# STM32F108VBT6_2.net
KiCad netlist of a schematic drawn in Altium Designer
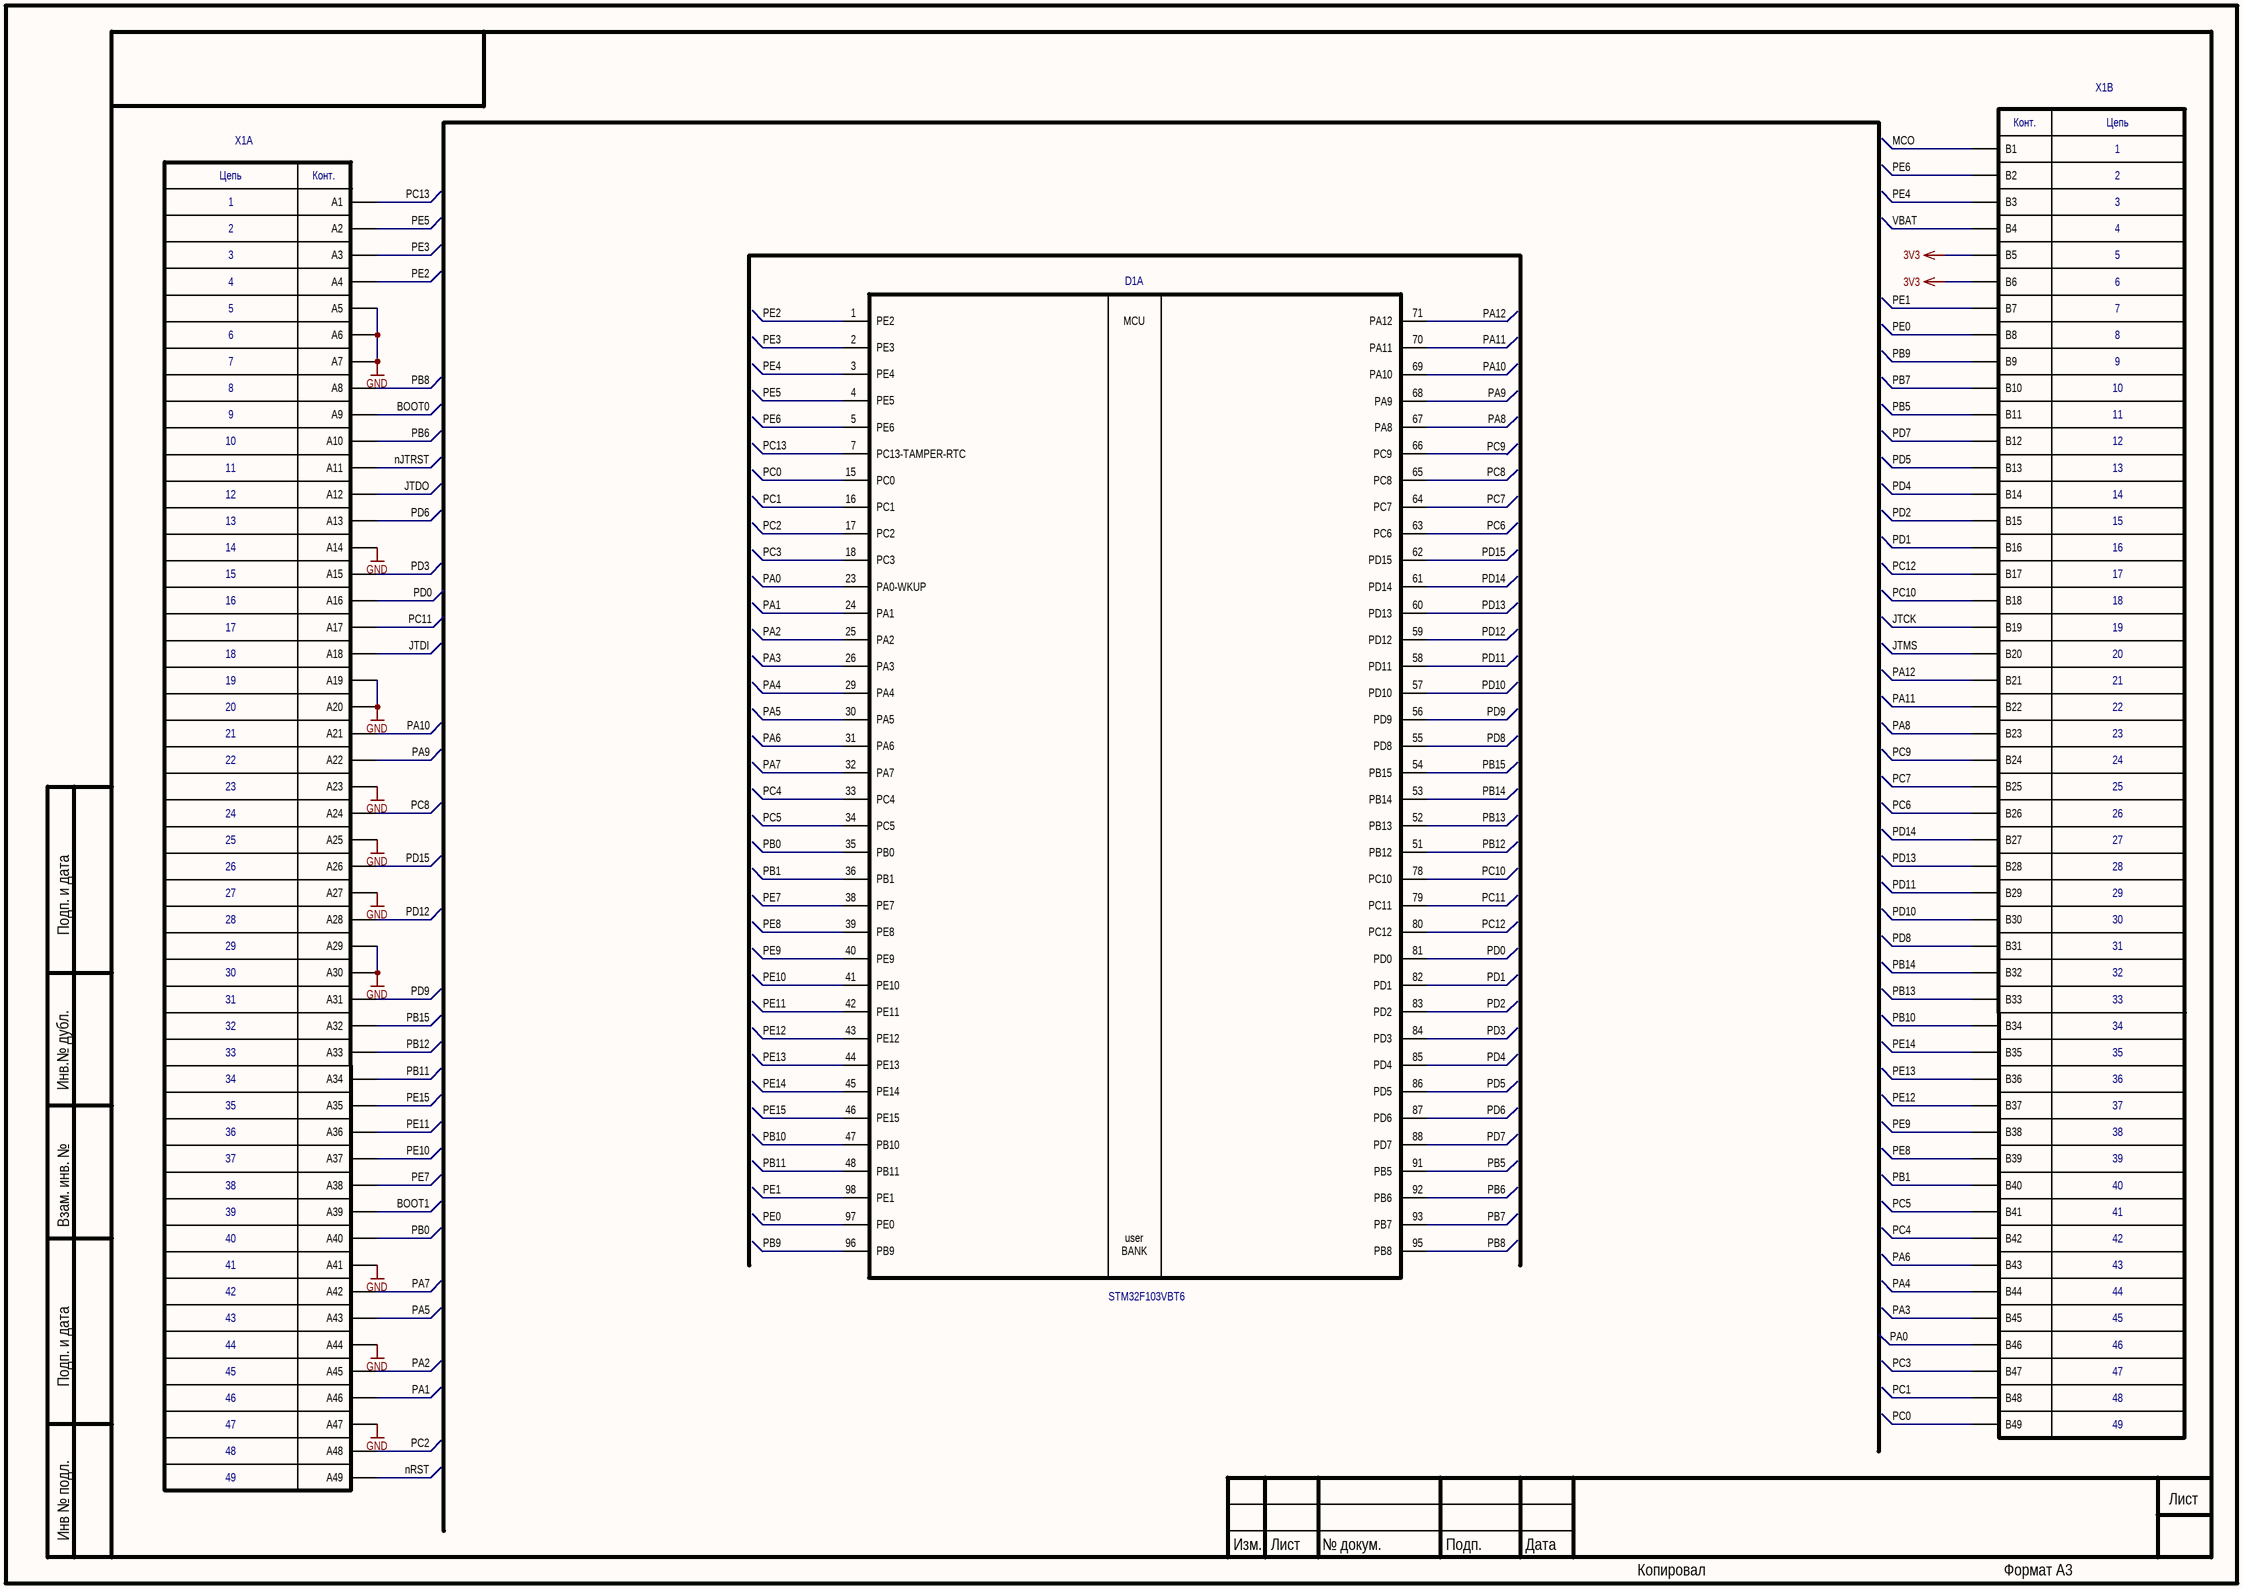
[diagram p0: Модуль STM32F108VBT6_2.SchDoc]

(export (version "E")
  (design (tool "Eeschema 10.0.6"))
  (components
    (comp (ref "D1")
      (value "STM32F103VBT6")
      (footprint "QFP50P1600X1600X160-100N")
      (fields (field (name "Comment") " (LQFP-48) Xilinx"))
      (libsource (lib "Lisaveta_SCH") (part "STM32F103VBT6"))
    )
    (comp (ref "X1")
      (value "KONT_POLE_MEZ")
      (footprint "3113-112t_otv")
      (libsource (lib "Lisaveta_SCH") (part "3113-112T"))
    )
  )
  (nets
    (net (code "1") (name "/BOOT0") (class "Default")
      (node (ref "X1") (pin "A9") (pinfunction "A9_A9") (pintype "passive"))
    )
    (net (code "2") (name "/BOOT1") (class "Default")
      (node (ref "X1") (pin "A39") (pinfunction "A39_A39") (pintype "passive"))
    )
    (net (code "3") (name "/JTCK") (class "Default")
      (node (ref "X1") (pin "B19") (pinfunction "B19_B19") (pintype "passive"))
    )
    (net (code "4") (name "/JTDI") (class "Default")
      (node (ref "X1") (pin "A18") (pinfunction "A18_A18") (pintype "passive"))
    )
    (net (code "5") (name "/JTDO") (class "Default")
      (node (ref "X1") (pin "A12") (pinfunction "A12_A12") (pintype "passive"))
    )
    (net (code "6") (name "/JTMS") (class "Default")
      (node (ref "X1") (pin "B20") (pinfunction "B20_B20") (pintype "passive"))
    )
    (net (code "7") (name "/MCO") (class "Default")
      (node (ref "X1") (pin "B1") (pinfunction "B1_B1") (pintype "passive"))
    )
    (net (code "8") (name "/PA0") (class "Default")
      (node (ref "D1") (pin "23") (pinfunction "PA0-WKUP_23") (pintype "passive"))
      (node (ref "X1") (pin "B46") (pinfunction "B46_B46") (pintype "passive"))
    )
    (net (code "9") (name "/PA1") (class "Default")
      (node (ref "D1") (pin "24") (pinfunction "PA1_24") (pintype "passive"))
      (node (ref "X1") (pin "A46") (pinfunction "A46_A46") (pintype "passive"))
    )
    (net (code "10") (name "/PA2") (class "Default")
      (node (ref "D1") (pin "25") (pinfunction "PA2_25") (pintype "passive"))
      (node (ref "X1") (pin "A45") (pinfunction "A45_A45") (pintype "passive"))
    )
    (net (code "11") (name "/PA3") (class "Default")
      (node (ref "D1") (pin "26") (pinfunction "PA3_26") (pintype "passive"))
      (node (ref "X1") (pin "B45") (pinfunction "B45_B45") (pintype "passive"))
    )
    (net (code "12") (name "/PA4") (class "Default")
      (node (ref "D1") (pin "29") (pinfunction "PA4_29") (pintype "passive"))
      (node (ref "X1") (pin "B44") (pinfunction "B44_B44") (pintype "passive"))
    )
    (net (code "13") (name "/PA5") (class "Default")
      (node (ref "D1") (pin "30") (pinfunction "PA5_30") (pintype "passive"))
      (node (ref "X1") (pin "A43") (pinfunction "A43_A43") (pintype "passive"))
    )
    (net (code "14") (name "/PA6") (class "Default")
      (node (ref "D1") (pin "31") (pinfunction "PA6_31") (pintype "passive"))
      (node (ref "X1") (pin "B43") (pinfunction "B43_B43") (pintype "passive"))
    )
    (net (code "15") (name "/PA7") (class "Default")
      (node (ref "D1") (pin "32") (pinfunction "PA7_32") (pintype "passive"))
      (node (ref "X1") (pin "A42") (pinfunction "A42_A42") (pintype "passive"))
    )
    (net (code "16") (name "/PA8") (class "Default")
      (node (ref "D1") (pin "67") (pinfunction "PA8_67") (pintype "passive"))
      (node (ref "X1") (pin "B23") (pinfunction "B23_B23") (pintype "passive"))
    )
    (net (code "17") (name "/PA9") (class "Default")
      (node (ref "D1") (pin "68") (pinfunction "PA9_68") (pintype "passive"))
      (node (ref "X1") (pin "A22") (pinfunction "A22_A22") (pintype "passive"))
    )
    (net (code "18") (name "/PA10") (class "Default")
      (node (ref "D1") (pin "69") (pinfunction "PA10_69") (pintype "passive"))
      (node (ref "X1") (pin "A21") (pinfunction "A21_A21") (pintype "passive"))
    )
    (net (code "19") (name "/PA11") (class "Default")
      (node (ref "D1") (pin "70") (pinfunction "PA11_70") (pintype "passive"))
      (node (ref "X1") (pin "B22") (pinfunction "B22_B22") (pintype "passive"))
    )
    (net (code "20") (name "/PA12") (class "Default")
      (node (ref "D1") (pin "71") (pinfunction "PA12_71") (pintype "passive"))
      (node (ref "X1") (pin "B21") (pinfunction "B21_B21") (pintype "passive"))
    )
    (net (code "21") (name "/PB0") (class "Default")
      (node (ref "D1") (pin "35") (pinfunction "PB0_35") (pintype "passive"))
      (node (ref "X1") (pin "A40") (pinfunction "A40_A40") (pintype "passive"))
    )
    (net (code "22") (name "/PB1") (class "Default")
      (node (ref "D1") (pin "36") (pinfunction "PB1_36") (pintype "passive"))
      (node (ref "X1") (pin "B40") (pinfunction "B40_B40") (pintype "passive"))
    )
    (net (code "23") (name "/PB5") (class "Default")
      (node (ref "D1") (pin "91") (pinfunction "PB5_91") (pintype "passive"))
      (node (ref "X1") (pin "B11") (pinfunction "B11_B11") (pintype "passive"))
    )
    (net (code "24") (name "/PB6") (class "Default")
      (node (ref "D1") (pin "92") (pinfunction "PB6_92") (pintype "passive"))
      (node (ref "X1") (pin "A10") (pinfunction "A10_A10") (pintype "passive"))
    )
    (net (code "25") (name "/PB7") (class "Default")
      (node (ref "D1") (pin "93") (pinfunction "PB7_93") (pintype "passive"))
      (node (ref "X1") (pin "B10") (pinfunction "B10_B10") (pintype "passive"))
    )
    (net (code "26") (name "/PB8") (class "Default")
      (node (ref "D1") (pin "95") (pinfunction "PB8_95") (pintype "passive"))
      (node (ref "X1") (pin "A8") (pinfunction "A8_A8") (pintype "passive"))
    )
    (net (code "27") (name "/PB9") (class "Default")
      (node (ref "D1") (pin "96") (pinfunction "PB9_96") (pintype "passive"))
      (node (ref "X1") (pin "B9") (pinfunction "B9_B9") (pintype "passive"))
    )
    (net (code "28") (name "/PB10") (class "Default")
      (node (ref "D1") (pin "47") (pinfunction "PB10_47") (pintype "passive"))
      (node (ref "X1") (pin "B34") (pinfunction "B34_B34") (pintype "passive"))
    )
    (net (code "29") (name "/PB11") (class "Default")
      (node (ref "D1") (pin "48") (pinfunction "PB11_48") (pintype "passive"))
      (node (ref "X1") (pin "A34") (pinfunction "A34_A34") (pintype "passive"))
    )
    (net (code "30") (name "/PB12") (class "Default")
      (node (ref "D1") (pin "51") (pinfunction "PB12_51") (pintype "passive"))
      (node (ref "X1") (pin "A33") (pinfunction "A33_A33") (pintype "passive"))
    )
    (net (code "31") (name "/PB13") (class "Default")
      (node (ref "D1") (pin "52") (pinfunction "PB13_52") (pintype "passive"))
      (node (ref "X1") (pin "B33") (pinfunction "B33_B33") (pintype "passive"))
    )
    (net (code "32") (name "/PB14") (class "Default")
      (node (ref "D1") (pin "53") (pinfunction "PB14_53") (pintype "passive"))
      (node (ref "X1") (pin "B32") (pinfunction "B32_B32") (pintype "passive"))
    )
    (net (code "33") (name "/PB15") (class "Default")
      (node (ref "D1") (pin "54") (pinfunction "PB15_54") (pintype "passive"))
      (node (ref "X1") (pin "A32") (pinfunction "A32_A32") (pintype "passive"))
    )
    (net (code "34") (name "/PC0") (class "Default")
      (node (ref "D1") (pin "15") (pinfunction "PC0_15") (pintype "passive"))
      (node (ref "X1") (pin "B49") (pinfunction "B49_B49") (pintype "passive"))
    )
    (net (code "35") (name "/PC1") (class "Default")
      (node (ref "D1") (pin "16") (pinfunction "PC1_16") (pintype "passive"))
      (node (ref "X1") (pin "B48") (pinfunction "B48_B48") (pintype "passive"))
    )
    (net (code "36") (name "/PC2") (class "Default")
      (node (ref "D1") (pin "17") (pinfunction "PC2_17") (pintype "passive"))
      (node (ref "X1") (pin "A48") (pinfunction "A48_A48") (pintype "passive"))
    )
    (net (code "37") (name "/PC3") (class "Default")
      (node (ref "D1") (pin "18") (pinfunction "PC3_18") (pintype "passive"))
      (node (ref "X1") (pin "B47") (pinfunction "B47_B47") (pintype "passive"))
    )
    (net (code "38") (name "/PC4") (class "Default")
      (node (ref "D1") (pin "33") (pinfunction "PC4_33") (pintype "passive"))
      (node (ref "X1") (pin "B42") (pinfunction "B42_B42") (pintype "passive"))
    )
    (net (code "39") (name "/PC5") (class "Default")
      (node (ref "D1") (pin "34") (pinfunction "PC5_34") (pintype "passive"))
      (node (ref "X1") (pin "B41") (pinfunction "B41_B41") (pintype "passive"))
    )
    (net (code "40") (name "/PC6") (class "Default")
      (node (ref "D1") (pin "63") (pinfunction "PC6_63") (pintype "passive"))
      (node (ref "X1") (pin "B26") (pinfunction "B26_B26") (pintype "passive"))
    )
    (net (code "41") (name "/PC7") (class "Default")
      (node (ref "D1") (pin "64") (pinfunction "PC7_64") (pintype "passive"))
      (node (ref "X1") (pin "B25") (pinfunction "B25_B25") (pintype "passive"))
    )
    (net (code "42") (name "/PC8") (class "Default")
      (node (ref "D1") (pin "65") (pinfunction "PC8_65") (pintype "passive"))
      (node (ref "X1") (pin "A24") (pinfunction "A24_A24") (pintype "passive"))
    )
    (net (code "43") (name "/PC9") (class "Default")
      (node (ref "D1") (pin "66") (pinfunction "PC9_66") (pintype "passive"))
      (node (ref "X1") (pin "B24") (pinfunction "B24_B24") (pintype "passive"))
    )
    (net (code "44") (name "/PC10") (class "Default")
      (node (ref "D1") (pin "78") (pinfunction "PC10_78") (pintype "passive"))
      (node (ref "X1") (pin "B18") (pinfunction "B18_B18") (pintype "passive"))
    )
    (net (code "45") (name "/PC11") (class "Default")
      (node (ref "D1") (pin "79") (pinfunction "PC11_79") (pintype "passive"))
      (node (ref "X1") (pin "A17") (pinfunction "A17_A17") (pintype "passive"))
    )
    (net (code "46") (name "/PC12") (class "Default")
      (node (ref "D1") (pin "80") (pinfunction "PC12_80") (pintype "passive"))
      (node (ref "X1") (pin "B17") (pinfunction "B17_B17") (pintype "passive"))
    )
    (net (code "47") (name "/PC13") (class "Default")
      (node (ref "D1") (pin "7") (pinfunction "PC13-TAMPER-RTC_7") (pintype "passive"))
      (node (ref "X1") (pin "A1") (pinfunction "A1_A1") (pintype "passive"))
    )
    (net (code "48") (name "/PD0") (class "Default")
      (node (ref "D1") (pin "81") (pinfunction "PD0_81") (pintype "passive"))
      (node (ref "X1") (pin "A16") (pinfunction "A16_A16") (pintype "passive"))
    )
    (net (code "49") (name "/PD1") (class "Default")
      (node (ref "D1") (pin "82") (pinfunction "PD1_82") (pintype "passive"))
      (node (ref "X1") (pin "B16") (pinfunction "B16_B16") (pintype "passive"))
    )
    (net (code "50") (name "/PD2") (class "Default")
      (node (ref "D1") (pin "83") (pinfunction "PD2_83") (pintype "passive"))
      (node (ref "X1") (pin "B15") (pinfunction "B15_B15") (pintype "passive"))
    )
    (net (code "51") (name "/PD3") (class "Default")
      (node (ref "D1") (pin "84") (pinfunction "PD3_84") (pintype "passive"))
      (node (ref "X1") (pin "A15") (pinfunction "A15_A15") (pintype "passive"))
    )
    (net (code "52") (name "/PD4") (class "Default")
      (node (ref "D1") (pin "85") (pinfunction "PD4_85") (pintype "passive"))
      (node (ref "X1") (pin "B14") (pinfunction "B14_B14") (pintype "passive"))
    )
    (net (code "53") (name "/PD5") (class "Default")
      (node (ref "D1") (pin "86") (pinfunction "PD5_86") (pintype "passive"))
      (node (ref "X1") (pin "B13") (pinfunction "B13_B13") (pintype "passive"))
    )
    (net (code "54") (name "/PD6") (class "Default")
      (node (ref "D1") (pin "87") (pinfunction "PD6_87") (pintype "passive"))
      (node (ref "X1") (pin "A13") (pinfunction "A13_A13") (pintype "passive"))
    )
    (net (code "55") (name "/PD7") (class "Default")
      (node (ref "D1") (pin "88") (pinfunction "PD7_88") (pintype "passive"))
      (node (ref "X1") (pin "B12") (pinfunction "B12_B12") (pintype "passive"))
    )
    (net (code "56") (name "/PD8") (class "Default")
      (node (ref "D1") (pin "55") (pinfunction "PD8_55") (pintype "passive"))
      (node (ref "X1") (pin "B31") (pinfunction "B31_B31") (pintype "passive"))
    )
    (net (code "57") (name "/PD9") (class "Default")
      (node (ref "D1") (pin "56") (pinfunction "PD9_56") (pintype "passive"))
      (node (ref "X1") (pin "A31") (pinfunction "A31_A31") (pintype "passive"))
    )
    (net (code "58") (name "/PD10") (class "Default")
      (node (ref "D1") (pin "57") (pinfunction "PD10_57") (pintype "passive"))
      (node (ref "X1") (pin "B30") (pinfunction "B30_B30") (pintype "passive"))
    )
    (net (code "59") (name "/PD11") (class "Default")
      (node (ref "D1") (pin "58") (pinfunction "PD11_58") (pintype "passive"))
      (node (ref "X1") (pin "B29") (pinfunction "B29_B29") (pintype "passive"))
    )
    (net (code "60") (name "/PD12") (class "Default")
      (node (ref "D1") (pin "59") (pinfunction "PD12_59") (pintype "passive"))
      (node (ref "X1") (pin "A28") (pinfunction "A28_A28") (pintype "passive"))
    )
    (net (code "61") (name "/PD13") (class "Default")
      (node (ref "D1") (pin "60") (pinfunction "PD13_60") (pintype "passive"))
      (node (ref "X1") (pin "B28") (pinfunction "B28_B28") (pintype "passive"))
    )
    (net (code "62") (name "/PD14") (class "Default")
      (node (ref "D1") (pin "61") (pinfunction "PD14_61") (pintype "passive"))
      (node (ref "X1") (pin "B27") (pinfunction "B27_B27") (pintype "passive"))
    )
    (net (code "63") (name "/PD15") (class "Default")
      (node (ref "D1") (pin "62") (pinfunction "PD15_62") (pintype "passive"))
      (node (ref "X1") (pin "A26") (pinfunction "A26_A26") (pintype "passive"))
    )
    (net (code "64") (name "/PE0") (class "Default")
      (node (ref "D1") (pin "97") (pinfunction "PE0_97") (pintype "passive"))
      (node (ref "X1") (pin "B8") (pinfunction "B8_B8") (pintype "passive"))
    )
    (net (code "65") (name "/PE1") (class "Default")
      (node (ref "D1") (pin "98") (pinfunction "PE1_98") (pintype "passive"))
      (node (ref "X1") (pin "B7") (pinfunction "B7_B7") (pintype "passive"))
    )
    (net (code "66") (name "/PE2") (class "Default")
      (node (ref "D1") (pin "1") (pinfunction "PE2_1") (pintype "passive"))
      (node (ref "X1") (pin "A4") (pinfunction "A4_A4") (pintype "passive"))
    )
    (net (code "67") (name "/PE3") (class "Default")
      (node (ref "D1") (pin "2") (pinfunction "PE3_2") (pintype "passive"))
      (node (ref "X1") (pin "A3") (pinfunction "A3_A3") (pintype "passive"))
    )
    (net (code "68") (name "/PE4") (class "Default")
      (node (ref "D1") (pin "3") (pinfunction "PE4_3") (pintype "passive"))
      (node (ref "X1") (pin "B3") (pinfunction "B3_B3") (pintype "passive"))
    )
    (net (code "69") (name "/PE5") (class "Default")
      (node (ref "D1") (pin "4") (pinfunction "PE5_4") (pintype "passive"))
      (node (ref "X1") (pin "A2") (pinfunction "A2_A2") (pintype "passive"))
    )
    (net (code "70") (name "/PE6") (class "Default")
      (node (ref "D1") (pin "5") (pinfunction "PE6_5") (pintype "passive"))
      (node (ref "X1") (pin "B2") (pinfunction "B2_B2") (pintype "passive"))
    )
    (net (code "71") (name "/PE7") (class "Default")
      (node (ref "D1") (pin "38") (pinfunction "PE7_38") (pintype "passive"))
      (node (ref "X1") (pin "A38") (pinfunction "A38_A38") (pintype "passive"))
    )
    (net (code "72") (name "/PE8") (class "Default")
      (node (ref "D1") (pin "39") (pinfunction "PE8_39") (pintype "passive"))
      (node (ref "X1") (pin "B39") (pinfunction "B39_B39") (pintype "passive"))
    )
    (net (code "73") (name "/PE9") (class "Default")
      (node (ref "D1") (pin "40") (pinfunction "PE9_40") (pintype "passive"))
      (node (ref "X1") (pin "B38") (pinfunction "B38_B38") (pintype "passive"))
    )
    (net (code "74") (name "/PE10") (class "Default")
      (node (ref "D1") (pin "41") (pinfunction "PE10_41") (pintype "passive"))
      (node (ref "X1") (pin "A37") (pinfunction "A37_A37") (pintype "passive"))
    )
    (net (code "75") (name "/PE11") (class "Default")
      (node (ref "D1") (pin "42") (pinfunction "PE11_42") (pintype "passive"))
      (node (ref "X1") (pin "A36") (pinfunction "A36_A36") (pintype "passive"))
    )
    (net (code "76") (name "/PE12") (class "Default")
      (node (ref "D1") (pin "43") (pinfunction "PE12_43") (pintype "passive"))
      (node (ref "X1") (pin "B37") (pinfunction "B37_B37") (pintype "passive"))
    )
    (net (code "77") (name "/PE13") (class "Default")
      (node (ref "D1") (pin "44") (pinfunction "PE13_44") (pintype "passive"))
      (node (ref "X1") (pin "B36") (pinfunction "B36_B36") (pintype "passive"))
    )
    (net (code "78") (name "/PE14") (class "Default")
      (node (ref "D1") (pin "45") (pinfunction "PE14_45") (pintype "passive"))
      (node (ref "X1") (pin "B35") (pinfunction "B35_B35") (pintype "passive"))
    )
    (net (code "79") (name "/PE15") (class "Default")
      (node (ref "D1") (pin "46") (pinfunction "PE15_46") (pintype "passive"))
      (node (ref "X1") (pin "A35") (pinfunction "A35_A35") (pintype "passive"))
    )
    (net (code "80") (name "/VBAT") (class "Default")
      (node (ref "X1") (pin "B4") (pinfunction "B4_B4") (pintype "passive"))
    )
    (net (code "81") (name "/nJTRST") (class "Default")
      (node (ref "X1") (pin "A11") (pinfunction "A11_A11") (pintype "passive"))
    )
    (net (code "82") (name "/nRST") (class "Default")
      (node (ref "X1") (pin "A49") (pinfunction "A49_A49") (pintype "passive"))
    )
    (net (code "83") (name "3V3") (class "Default")
      (node (ref "X1") (pin "B5") (pinfunction "B5_B5") (pintype "passive"))
      (node (ref "X1") (pin "B6") (pinfunction "B6_B6") (pintype "passive"))
    )
    (net (code "84") (name "GND") (class "Default")
      (node (ref "X1") (pin "A14") (pinfunction "A14_A14") (pintype "passive"))
      (node (ref "X1") (pin "A19") (pinfunction "A19_A19") (pintype "passive"))
      (node (ref "X1") (pin "A20") (pinfunction "A20_A20") (pintype "passive"))
      (node (ref "X1") (pin "A23") (pinfunction "A23_A23") (pintype "passive"))
      (node (ref "X1") (pin "A25") (pinfunction "A25_A25") (pintype "passive"))
      (node (ref "X1") (pin "A27") (pinfunction "A27_A27") (pintype "passive"))
      (node (ref "X1") (pin "A29") (pinfunction "A29_A29") (pintype "passive"))
      (node (ref "X1") (pin "A30") (pinfunction "A30_A30") (pintype "passive"))
      (node (ref "X1") (pin "A41") (pinfunction "A41_A41") (pintype "passive"))
      (node (ref "X1") (pin "A44") (pinfunction "A44_A44") (pintype "passive"))
      (node (ref "X1") (pin "A47") (pinfunction "A47_A47") (pintype "passive"))
      (node (ref "X1") (pin "A5") (pinfunction "A5_A5") (pintype "passive"))
      (node (ref "X1") (pin "A6") (pinfunction "A6_A6") (pintype "passive"))
      (node (ref "X1") (pin "A7") (pinfunction "A7_A7") (pintype "passive"))
    )
  )
)
